# HF_Voltage_Transformer.net
KiCad netlist of a schematic drawn in Altium Designer
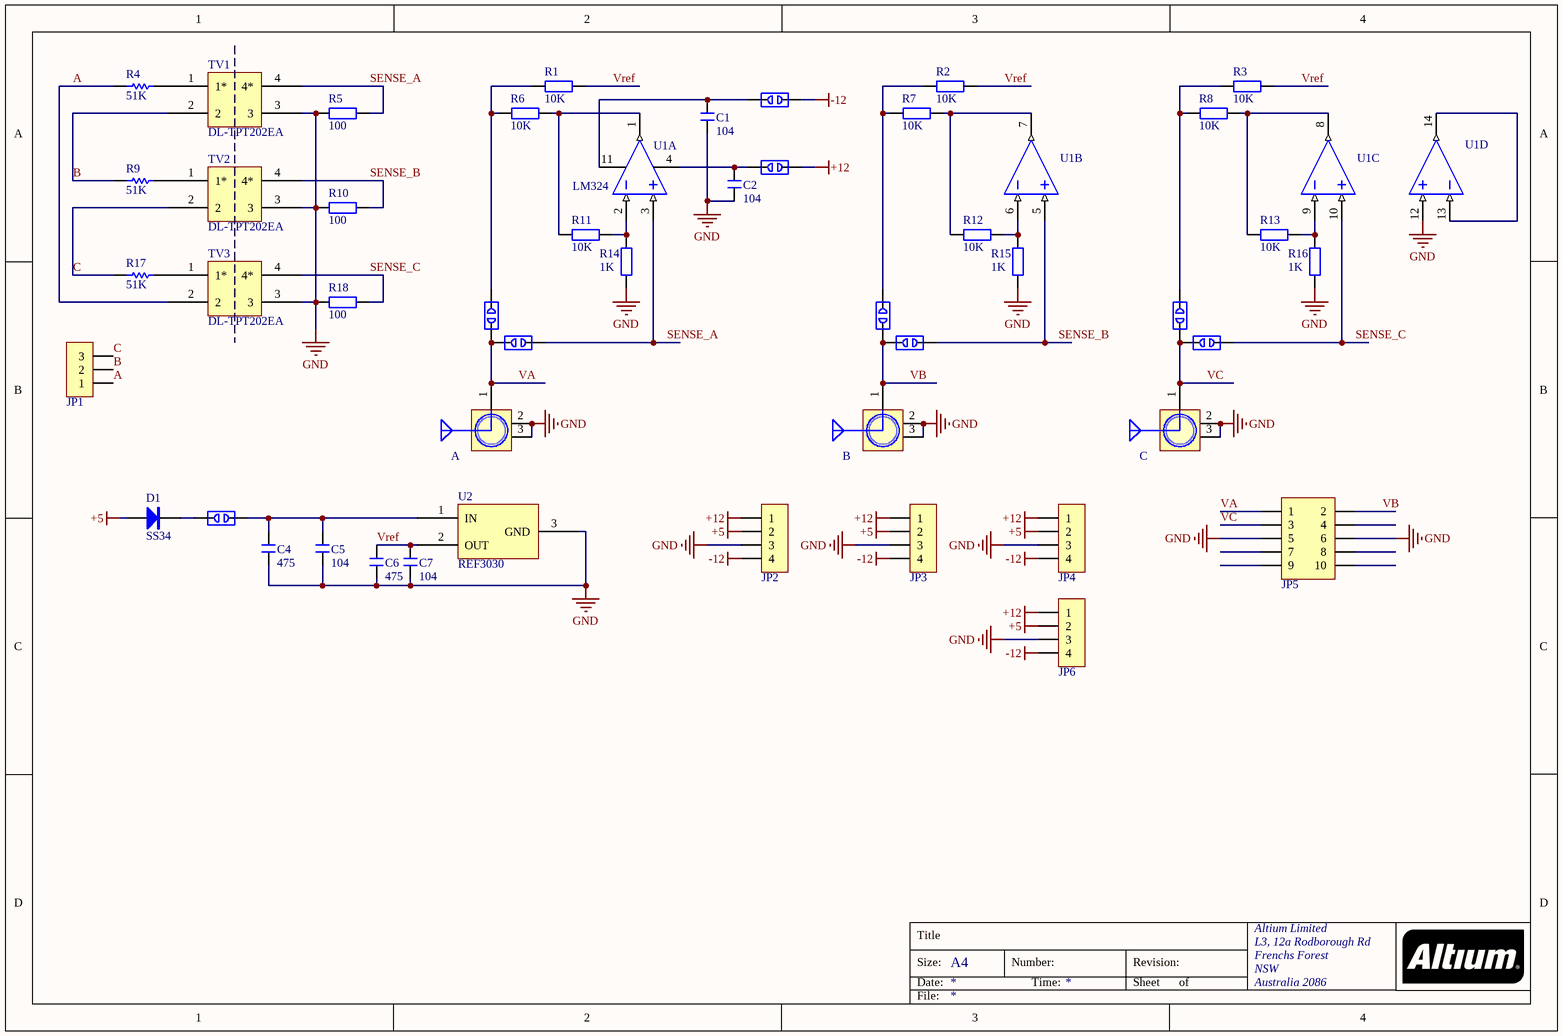
[diagram p0: HF_Voltage_Transformer.SchDoc]

(export (version "E")
  (design (tool "Eeschema 10.0.6"))
  (components
    (comp (ref "A")
      (value "SMA WIFI 天线接口")
      (footprint "SMA-KE-LI")
      (description "SMA-2.4G射频天线接口")
      (libsource (lib "04 - 接口类-USB接口-网口") (part "SMA WIFI"))
    )
    (comp (ref "B")
      (value "SMA WIFI 天线接口")
      (footprint "SMA-KE-LI")
      (description "SMA-2.4G射频天线接口")
      (libsource (lib "04 - 接口类-USB接口-网口") (part "SMA WIFI"))
    )
    (comp (ref "C")
      (value "SMA WIFI 天线接口")
      (footprint "SMA-KE-LI")
      (description "SMA-2.4G射频天线接口")
      (libsource (lib "04 - 接口类-USB接口-网口") (part "SMA WIFI"))
    )
    (comp (ref "C1")
      (value "104")
      (footprint "C 0805_L")
      (description "贴片电容")
      (libsource (lib "01 - 电容-电阻-电感") (part "C"))
    )
    (comp (ref "C2")
      (value "104")
      (footprint "C 0805_L")
      (description "贴片电容")
      (libsource (lib "01 - 电容-电阻-电感") (part "C"))
    )
    (comp (ref "C4")
      (value "475")
      (footprint "C 0805_L")
      (description "贴片电容")
      (libsource (lib "01 - 电容-电阻-电感") (part "C"))
    )
    (comp (ref "C5")
      (value "104")
      (footprint "C 0805_L")
      (description "贴片电容")
      (libsource (lib "01 - 电容-电阻-电感") (part "C"))
    )
    (comp (ref "C6")
      (value "475")
      (footprint "C 0805_L")
      (description "贴片电容")
      (libsource (lib "01 - 电容-电阻-电感") (part "C"))
    )
    (comp (ref "C7")
      (value "104")
      (footprint "C 0805_L")
      (description "贴片电容")
      (libsource (lib "01 - 电容-电阻-电感") (part "C"))
    )
    (comp (ref "D1")
      (value "SS34")
      (footprint "SMA")
      (description "整流二极管")
      (libsource (lib "02 - 二极管(LED)-三极管-整流桥") (part "1N4007"))
    )
    (comp (ref "DE1")
      (value "DEBUG PAD")
      (footprint "DEBUG_B")
      (description "调试断点焊盘")
      (libsource (lib "10 - 未分类元器件") (part "DEBUG"))
    )
    (comp (ref "DE2")
      (value "DEBUG PAD")
      (footprint "DEBUG_B")
      (description "调试断点焊盘")
      (libsource (lib "10 - 未分类元器件") (part "DEBUG"))
    )
    (comp (ref "DE3")
      (value "DEBUG PAD")
      (footprint "DEBUG_B")
      (description "调试断点焊盘")
      (libsource (lib "") (part "DEBUG_1"))
    )
    (comp (ref "DE4")
      (value "DEBUG PAD")
      (footprint "DEBUG_B")
      (description "调试断点焊盘")
      (libsource (lib "") (part "DEBUG_1"))
    )
    (comp (ref "DE5")
      (value "DEBUG PAD")
      (footprint "DEBUG_B")
      (description "调试断点焊盘")
      (libsource (lib "") (part "DEBUG_1"))
    )
    (comp (ref "DE6")
      (value "DEBUG PAD")
      (footprint "DEBUG_B")
      (description "调试断点焊盘")
      (libsource (lib "10 - 未分类元器件") (part "DEBUG"))
    )
    (comp (ref "DE7")
      (value "DEBUG PAD")
      (footprint "DEBUG_B")
      (description "调试断点焊盘")
      (libsource (lib "10 - 未分类元器件") (part "DEBUG"))
    )
    (comp (ref "DE8")
      (value "DEBUG PAD")
      (footprint "DEBUG_B")
      (description "调试断点焊盘")
      (libsource (lib "10 - 未分类元器件") (part "DEBUG"))
    )
    (comp (ref "DE9")
      (value "DEBUG PAD")
      (footprint "DEBUG_B")
      (description "调试断点焊盘")
      (libsource (lib "10 - 未分类元器件") (part "DEBUG"))
    )
    (comp (ref "JP1")
      (value "HDR-1X3")
      (footprint "KF7620-3P")
      (description "3P接插件")
      (libsource (lib "24 - 接插件-脚距7.62mm (300mil) ") (part "Header 3"))
    )
    (comp (ref "JP2")
      (value "HDR-1X4")
      (footprint "KF2510-LI-4P")
      (description "4P接插件")
      (libsource (lib "18 - 接插件-脚距2.54mm (100mil) ") (part "Header 4"))
    )
    (comp (ref "JP3")
      (value "HDR-1X4")
      (footprint "KF2510-LI-4P")
      (description "4P接插件")
      (libsource (lib "18 - 接插件-脚距2.54mm (100mil) ") (part "Header 4"))
    )
    (comp (ref "JP4")
      (value "HDR-1X4")
      (footprint "KF2510-LI-4P")
      (description "4P接插件")
      (libsource (lib "18 - 接插件-脚距2.54mm (100mil) ") (part "Header 4"))
    )
    (comp (ref "JP5")
      (value "Header 5X2")
      (footprint "IDC2.54-LI-2x5P")
      (description "5*2P接插件")
      (libsource (lib "18 - 接插件-脚距2.54mm (100mil) ") (part "Header 5X2"))
    )
    (comp (ref "JP6")
      (value "HDR-1X4")
      (footprint "KF2510-LI-4P")
      (description "4P接插件")
      (libsource (lib "18 - 接插件-脚距2.54mm (100mil) ") (part "Header 4"))
    )
    (comp (ref "R1")
      (value "10K")
      (footprint "R 0805_L")
      (description "贴片电阻")
      (libsource (lib "01 - 电容-电阻-电感") (part "R"))
    )
    (comp (ref "R2")
      (value "10K")
      (footprint "R 0805_L")
      (description "贴片电阻")
      (libsource (lib "01 - 电容-电阻-电感") (part "R"))
    )
    (comp (ref "R3")
      (value "10K")
      (footprint "R 0805_L")
      (description "贴片电阻")
      (libsource (lib "01 - 电容-电阻-电感") (part "R"))
    )
    (comp (ref "R4")
      (value "51K")
      (footprint "RS 2W-V6")
      (description "色环电阻")
      (libsource (lib "01 - 电容-电阻-电感") (part "Res"))
    )
    (comp (ref "R5")
      (value "100")
      (footprint "R 0805_M")
      (description "贴片电阻")
      (libsource (lib "01 - 电容-电阻-电感") (part "R"))
    )
    (comp (ref "R6")
      (value "10K")
      (footprint "R 0805_L")
      (description "贴片电阻")
      (libsource (lib "01 - 电容-电阻-电感") (part "R"))
    )
    (comp (ref "R7")
      (value "10K")
      (footprint "R 0805_L")
      (description "贴片电阻")
      (libsource (lib "01 - 电容-电阻-电感") (part "R"))
    )
    (comp (ref "R8")
      (value "10K")
      (footprint "R 0805_L")
      (description "贴片电阻")
      (libsource (lib "01 - 电容-电阻-电感") (part "R"))
    )
    (comp (ref "R9")
      (value "51K")
      (footprint "RS 2W-V6")
      (description "色环电阻")
      (libsource (lib "01 - 电容-电阻-电感") (part "Res"))
    )
    (comp (ref "R10")
      (value "100")
      (footprint "R 0805_M")
      (description "贴片电阻")
      (libsource (lib "01 - 电容-电阻-电感") (part "R"))
    )
    (comp (ref "R11")
      (value "10K")
      (footprint "R 0805_L")
      (description "贴片电阻")
      (libsource (lib "01 - 电容-电阻-电感") (part "R"))
    )
    (comp (ref "R12")
      (value "10K")
      (footprint "R 0805_L")
      (description "贴片电阻")
      (libsource (lib "01 - 电容-电阻-电感") (part "R"))
    )
    (comp (ref "R13")
      (value "10K")
      (footprint "R 0805_L")
      (description "贴片电阻")
      (libsource (lib "01 - 电容-电阻-电感") (part "R"))
    )
    (comp (ref "R14")
      (value "1K")
      (footprint "R 0805_L")
      (description "贴片电阻")
      (libsource (lib "01 - 电容-电阻-电感") (part "R"))
    )
    (comp (ref "R15")
      (value "1K")
      (footprint "R 0805_L")
      (description "贴片电阻")
      (libsource (lib "01 - 电容-电阻-电感") (part "R"))
    )
    (comp (ref "R16")
      (value "1K")
      (footprint "R 0805_L")
      (description "贴片电阻")
      (libsource (lib "01 - 电容-电阻-电感") (part "R"))
    )
    (comp (ref "R17")
      (value "51K")
      (footprint "RS 2W-V6")
      (description "色环电阻")
      (libsource (lib "01 - 电容-电阻-电感") (part "Res"))
    )
    (comp (ref "R18")
      (value "100")
      (footprint "R 0805_M")
      (description "贴片电阻")
      (libsource (lib "01 - 电容-电阻-电感") (part "R"))
    )
    (comp (ref "TV1")
      (value "DL-TPT202EA")
      (footprint "DL-TPT202EA")
      (description "高频电压互感器 - 南京向上 - 2mA/2mA")
      (libsource (lib "09 - 各种传感器(传感元器件)") (part "DL-TPT202EA"))
    )
    (comp (ref "TV2")
      (value "DL-TPT202EA")
      (footprint "DL-TPT202EA")
      (description "高频电压互感器 - 南京向上 - 2mA/2mA")
      (libsource (lib "09 - 各种传感器(传感元器件)") (part "DL-TPT202EA"))
    )
    (comp (ref "TV3")
      (value "DL-TPT202EA")
      (footprint "DL-TPT202EA")
      (description "高频电压互感器 - 南京向上 - 2mA/2mA")
      (libsource (lib "09 - 各种传感器(传感元器件)") (part "DL-TPT202EA"))
    )
    (comp (ref "U1")
      (value "LM324")
      (footprint "SOIC-14")
      (description "4路运放")
      (libsource (lib "11 - 运放-ADC") (part "LM324"))
    )
    (comp (ref "U2") (value "REF3030") (footprint "SOT23-3L") (libsource (lib "08 - 电压基准") (part "REF3030")))
  )
  (nets
    (net (code "1") (name "+5") (class "Default")
      (node (ref "D1") (pin "1") (pinfunction "A_1") (pintype "passive"))
      (node (ref "JP2") (pin "2") (pinfunction "2_2") (pintype "passive"))
      (node (ref "JP3") (pin "2") (pinfunction "2_2") (pintype "passive"))
      (node (ref "JP4") (pin "2") (pinfunction "2_2") (pintype "passive"))
      (node (ref "JP6") (pin "2") (pinfunction "2_2") (pintype "passive"))
    )
    (net (code "2") (name "+12") (class "Default")
      (node (ref "DE2") (pin "1") (pinfunction "1_1") (pintype "passive"))
      (node (ref "JP2") (pin "1") (pinfunction "1_1") (pintype "passive"))
      (node (ref "JP3") (pin "1") (pinfunction "1_1") (pintype "passive"))
      (node (ref "JP4") (pin "1") (pinfunction "1_1") (pintype "passive"))
      (node (ref "JP6") (pin "1") (pinfunction "1_1") (pintype "passive"))
    )
    (net (code "3") (name "-12") (class "Default")
      (node (ref "DE1") (pin "1") (pinfunction "1_1") (pintype "passive"))
      (node (ref "JP2") (pin "4") (pinfunction "4_4") (pintype "passive"))
      (node (ref "JP3") (pin "4") (pinfunction "4_4") (pintype "passive"))
      (node (ref "JP4") (pin "4") (pinfunction "4_4") (pintype "passive"))
      (node (ref "JP6") (pin "4") (pinfunction "4_4") (pintype "passive"))
    )
    (net (code "4") (name "/A") (class "Default")
      (node (ref "JP1") (pin "1") (pinfunction "1_1") (pintype "passive"))
      (node (ref "R4") (pin "1") (pinfunction "1_1") (pintype "passive"))
      (node (ref "TV3") (pin "2") (pinfunction "2_2") (pintype "passive"))
    )
    (net (code "5") (name "/B") (class "Default")
      (node (ref "JP1") (pin "2") (pinfunction "2_2") (pintype "passive"))
      (node (ref "R9") (pin "1") (pinfunction "1_1") (pintype "passive"))
      (node (ref "TV1") (pin "2") (pinfunction "2_2") (pintype "passive"))
    )
    (net (code "6") (name "/C") (class "Default")
      (node (ref "JP1") (pin "3") (pinfunction "3_3") (pintype "passive"))
      (node (ref "R17") (pin "1") (pinfunction "1_1") (pintype "passive"))
      (node (ref "TV2") (pin "2") (pinfunction "2_2") (pintype "passive"))
    )
    (net (code "7") (name "/SENSE_A") (class "Default")
      (node (ref "DE6") (pin "1") (pinfunction "1_1") (pintype "passive"))
      (node (ref "R5") (pin "2") (pinfunction "2_2") (pintype "passive"))
      (node (ref "TV1") (pin "4") (pinfunction "4*_4") (pintype "passive"))
      (node (ref "U1") (pin "3") (pinfunction "IN+_3") (pintype "input"))
    )
    (net (code "8") (name "/SENSE_B") (class "Default")
      (node (ref "DE7") (pin "1") (pinfunction "1_1") (pintype "passive"))
      (node (ref "R10") (pin "2") (pinfunction "2_2") (pintype "passive"))
      (node (ref "TV2") (pin "4") (pinfunction "4*_4") (pintype "passive"))
      (node (ref "U1") (pin "5") (pinfunction "IN+_5") (pintype "input"))
    )
    (net (code "9") (name "/SENSE_C") (class "Default")
      (node (ref "DE8") (pin "1") (pinfunction "1_1") (pintype "passive"))
      (node (ref "R18") (pin "2") (pinfunction "2_2") (pintype "passive"))
      (node (ref "TV3") (pin "4") (pinfunction "4*_4") (pintype "passive"))
      (node (ref "U1") (pin "10") (pinfunction "IN+_10") (pintype "input"))
    )
    (net (code "10") (name "/VA") (class "Default")
      (node (ref "A") (pin "1") (pinfunction "ANT_1") (pintype "passive"))
      (node (ref "DE3") (pin "1") (pinfunction "1_1") (pintype "passive"))
      (node (ref "DE6") (pin "2") (pinfunction "2_2") (pintype "passive"))
      (node (ref "JP5") (pin "1") (pinfunction "1_1") (pintype "passive"))
    )
    (net (code "11") (name "/VB") (class "Default")
      (node (ref "B") (pin "1") (pinfunction "ANT_1") (pintype "passive"))
      (node (ref "DE4") (pin "1") (pinfunction "1_1") (pintype "passive"))
      (node (ref "DE7") (pin "2") (pinfunction "2_2") (pintype "passive"))
      (node (ref "JP5") (pin "2") (pinfunction "2_2") (pintype "passive"))
    )
    (net (code "12") (name "/VC") (class "Default")
      (node (ref "C") (pin "1") (pinfunction "ANT_1") (pintype "passive"))
      (node (ref "DE5") (pin "1") (pinfunction "1_1") (pintype "passive"))
      (node (ref "DE8") (pin "2") (pinfunction "2_2") (pintype "passive"))
      (node (ref "JP5") (pin "3") (pinfunction "3_3") (pintype "passive"))
    )
    (net (code "13") (name "/Vref") (class "Default")
      (node (ref "C6") (pin "2") (pinfunction "2_2") (pintype "passive"))
      (node (ref "C7") (pin "2") (pinfunction "2_2") (pintype "passive"))
      (node (ref "R1") (pin "1") (pinfunction "1_1") (pintype "passive"))
      (node (ref "R2") (pin "1") (pinfunction "1_1") (pintype "passive"))
      (node (ref "R3") (pin "1") (pinfunction "1_1") (pintype "passive"))
      (node (ref "U2") (pin "2") (pinfunction "OUT_2") (pintype "passive"))
    )
    (net (code "14") (name "GND") (class "Default")
      (node (ref "A") (pin "2") (pinfunction "GND_2") (pintype "passive"))
      (node (ref "A") (pin "3") (pinfunction "GND_3") (pintype "passive"))
      (node (ref "B") (pin "2") (pinfunction "GND_2") (pintype "passive"))
      (node (ref "B") (pin "3") (pinfunction "GND_3") (pintype "passive"))
      (node (ref "C") (pin "2") (pinfunction "GND_2") (pintype "passive"))
      (node (ref "C") (pin "3") (pinfunction "GND_3") (pintype "passive"))
      (node (ref "C1") (pin "1") (pinfunction "1_1") (pintype "passive"))
      (node (ref "C2") (pin "1") (pinfunction "1_1") (pintype "passive"))
      (node (ref "C4") (pin "1") (pinfunction "1_1") (pintype "passive"))
      (node (ref "C5") (pin "1") (pinfunction "1_1") (pintype "passive"))
      (node (ref "C6") (pin "1") (pinfunction "1_1") (pintype "passive"))
      (node (ref "C7") (pin "1") (pinfunction "1_1") (pintype "passive"))
      (node (ref "JP2") (pin "3") (pinfunction "3_3") (pintype "passive"))
      (node (ref "JP3") (pin "3") (pinfunction "3_3") (pintype "passive"))
      (node (ref "JP4") (pin "3") (pinfunction "3_3") (pintype "passive"))
      (node (ref "JP5") (pin "5") (pinfunction "5_5") (pintype "passive"))
      (node (ref "JP5") (pin "6") (pinfunction "6_6") (pintype "passive"))
      (node (ref "JP6") (pin "3") (pinfunction "3_3") (pintype "passive"))
      (node (ref "R10") (pin "1") (pinfunction "1_1") (pintype "passive"))
      (node (ref "R14") (pin "1") (pinfunction "1_1") (pintype "passive"))
      (node (ref "R15") (pin "1") (pinfunction "1_1") (pintype "passive"))
      (node (ref "R16") (pin "1") (pinfunction "1_1") (pintype "passive"))
      (node (ref "R18") (pin "1") (pinfunction "1_1") (pintype "passive"))
      (node (ref "R5") (pin "1") (pinfunction "1_1") (pintype "passive"))
      (node (ref "TV1") (pin "3") (pinfunction "3_3") (pintype "passive"))
      (node (ref "TV2") (pin "3") (pinfunction "3_3") (pintype "passive"))
      (node (ref "TV3") (pin "3") (pinfunction "3_3") (pintype "passive"))
      (node (ref "U1") (pin "12") (pinfunction "IN+_12") (pintype "input"))
      (node (ref "U2") (pin "3") (pinfunction "GND_3") (pintype "passive"))
    )
    (net (code "15") (name "Net-(D1-K)") (class "Default")
      (node (ref "D1") (pin "2") (pinfunction "K_2") (pintype "passive"))
      (node (ref "DE9") (pin "1") (pinfunction "1_1") (pintype "passive"))
    )
    (net (code "16") (name "Net-(DE3-Pad2)") (class "Default")
      (node (ref "DE3") (pin "2") (pinfunction "2_2") (pintype "passive"))
      (node (ref "R1") (pin "2") (pinfunction "2_2") (pintype "passive"))
      (node (ref "R6") (pin "1") (pinfunction "1_1") (pintype "passive"))
    )
    (net (code "17") (name "Net-(DE4-Pad2)") (class "Default")
      (node (ref "DE4") (pin "2") (pinfunction "2_2") (pintype "passive"))
      (node (ref "R2") (pin "2") (pinfunction "2_2") (pintype "passive"))
      (node (ref "R7") (pin "1") (pinfunction "1_1") (pintype "passive"))
    )
    (net (code "18") (name "Net-(DE5-Pad2)") (class "Default")
      (node (ref "DE5") (pin "2") (pinfunction "2_2") (pintype "passive"))
      (node (ref "R3") (pin "2") (pinfunction "2_2") (pintype "passive"))
      (node (ref "R8") (pin "1") (pinfunction "1_1") (pintype "passive"))
    )
    (net (code "19") (name "Net-(TV1-1*)") (class "Default")
      (node (ref "R4") (pin "2") (pinfunction "2_2") (pintype "passive"))
      (node (ref "TV1") (pin "1") (pinfunction "1*_1") (pintype "passive"))
    )
    (net (code "20") (name "Net-(TV2-1*)") (class "Default")
      (node (ref "R9") (pin "2") (pinfunction "2_2") (pintype "passive"))
      (node (ref "TV2") (pin "1") (pinfunction "1*_1") (pintype "passive"))
    )
    (net (code "21") (name "Net-(TV3-1*)") (class "Default")
      (node (ref "R17") (pin "2") (pinfunction "2_2") (pintype "passive"))
      (node (ref "TV3") (pin "1") (pinfunction "1*_1") (pintype "passive"))
    )
    (net (code "22") (name "Net-(U1A-IN-)") (class "Default")
      (node (ref "R11") (pin "2") (pinfunction "2_2") (pintype "passive"))
      (node (ref "R14") (pin "2") (pinfunction "2_2") (pintype "passive"))
      (node (ref "U1") (pin "2") (pinfunction "IN-_2") (pintype "input"))
    )
    (net (code "23") (name "Net-(U1A-OUT)") (class "Default")
      (node (ref "R11") (pin "1") (pinfunction "1_1") (pintype "passive"))
      (node (ref "R6") (pin "2") (pinfunction "2_2") (pintype "passive"))
      (node (ref "U1") (pin "1") (pinfunction "OUT_1") (pintype "output"))
    )
    (net (code "24") (name "Net-(U1A-V+)") (class "Default")
      (node (ref "C2") (pin "2") (pinfunction "2_2") (pintype "passive"))
      (node (ref "DE2") (pin "2") (pinfunction "2_2") (pintype "passive"))
      (node (ref "U1") (pin "4") (pinfunction "V+_4") (pintype "passive"))
    )
    (net (code "25") (name "Net-(U1A-V-)") (class "Default")
      (node (ref "C1") (pin "2") (pinfunction "2_2") (pintype "passive"))
      (node (ref "DE1") (pin "2") (pinfunction "2_2") (pintype "passive"))
      (node (ref "U1") (pin "11") (pinfunction "V-_11") (pintype "passive"))
    )
    (net (code "26") (name "Net-(U1B-IN-)") (class "Default")
      (node (ref "R12") (pin "2") (pinfunction "2_2") (pintype "passive"))
      (node (ref "R15") (pin "2") (pinfunction "2_2") (pintype "passive"))
      (node (ref "U1") (pin "6") (pinfunction "IN-_6") (pintype "input"))
    )
    (net (code "27") (name "Net-(U1B-OUT)") (class "Default")
      (node (ref "R12") (pin "1") (pinfunction "1_1") (pintype "passive"))
      (node (ref "R7") (pin "2") (pinfunction "2_2") (pintype "passive"))
      (node (ref "U1") (pin "7") (pinfunction "OUT_7") (pintype "output"))
    )
    (net (code "28") (name "Net-(U1C-IN-)") (class "Default")
      (node (ref "R13") (pin "2") (pinfunction "2_2") (pintype "passive"))
      (node (ref "R16") (pin "2") (pinfunction "2_2") (pintype "passive"))
      (node (ref "U1") (pin "9") (pinfunction "IN-_9") (pintype "input"))
    )
    (net (code "29") (name "Net-(U1C-OUT)") (class "Default")
      (node (ref "R13") (pin "1") (pinfunction "1_1") (pintype "passive"))
      (node (ref "R8") (pin "2") (pinfunction "2_2") (pintype "passive"))
      (node (ref "U1") (pin "8") (pinfunction "OUT_8") (pintype "output"))
    )
    (net (code "30") (name "Net-(U1D-IN-)") (class "Default")
      (node (ref "U1") (pin "13") (pinfunction "IN-_13") (pintype "input"))
      (node (ref "U1") (pin "14") (pinfunction "OUT_14") (pintype "output"))
    )
    (net (code "31") (name "Net-(U2-IN)") (class "Default")
      (node (ref "C4") (pin "2") (pinfunction "2_2") (pintype "passive"))
      (node (ref "C5") (pin "2") (pinfunction "2_2") (pintype "passive"))
      (node (ref "DE9") (pin "2") (pinfunction "2_2") (pintype "passive"))
      (node (ref "U2") (pin "1") (pinfunction "IN_1") (pintype "passive"))
    )
    (net (code "32") (name "unconnected-(JP5-Pad4)") (class "Default")
      (node (ref "JP5") (pin "4") (pinfunction "4_4") (pintype "passive"))
    )
    (net (code "33") (name "unconnected-(JP5-Pad7)") (class "Default")
      (node (ref "JP5") (pin "7") (pinfunction "7_7") (pintype "passive"))
    )
    (net (code "34") (name "unconnected-(JP5-Pad8)") (class "Default")
      (node (ref "JP5") (pin "8") (pinfunction "8_8") (pintype "passive"))
    )
    (net (code "35") (name "unconnected-(JP5-Pad9)") (class "Default")
      (node (ref "JP5") (pin "9") (pinfunction "9_9") (pintype "passive"))
    )
    (net (code "36") (name "unconnected-(JP5-Pad10)") (class "Default")
      (node (ref "JP5") (pin "10") (pinfunction "10_10") (pintype "passive"))
    )
  )
)
